# cominer_serial.net
KiCad netlist of a schematic drawn in EAGLE
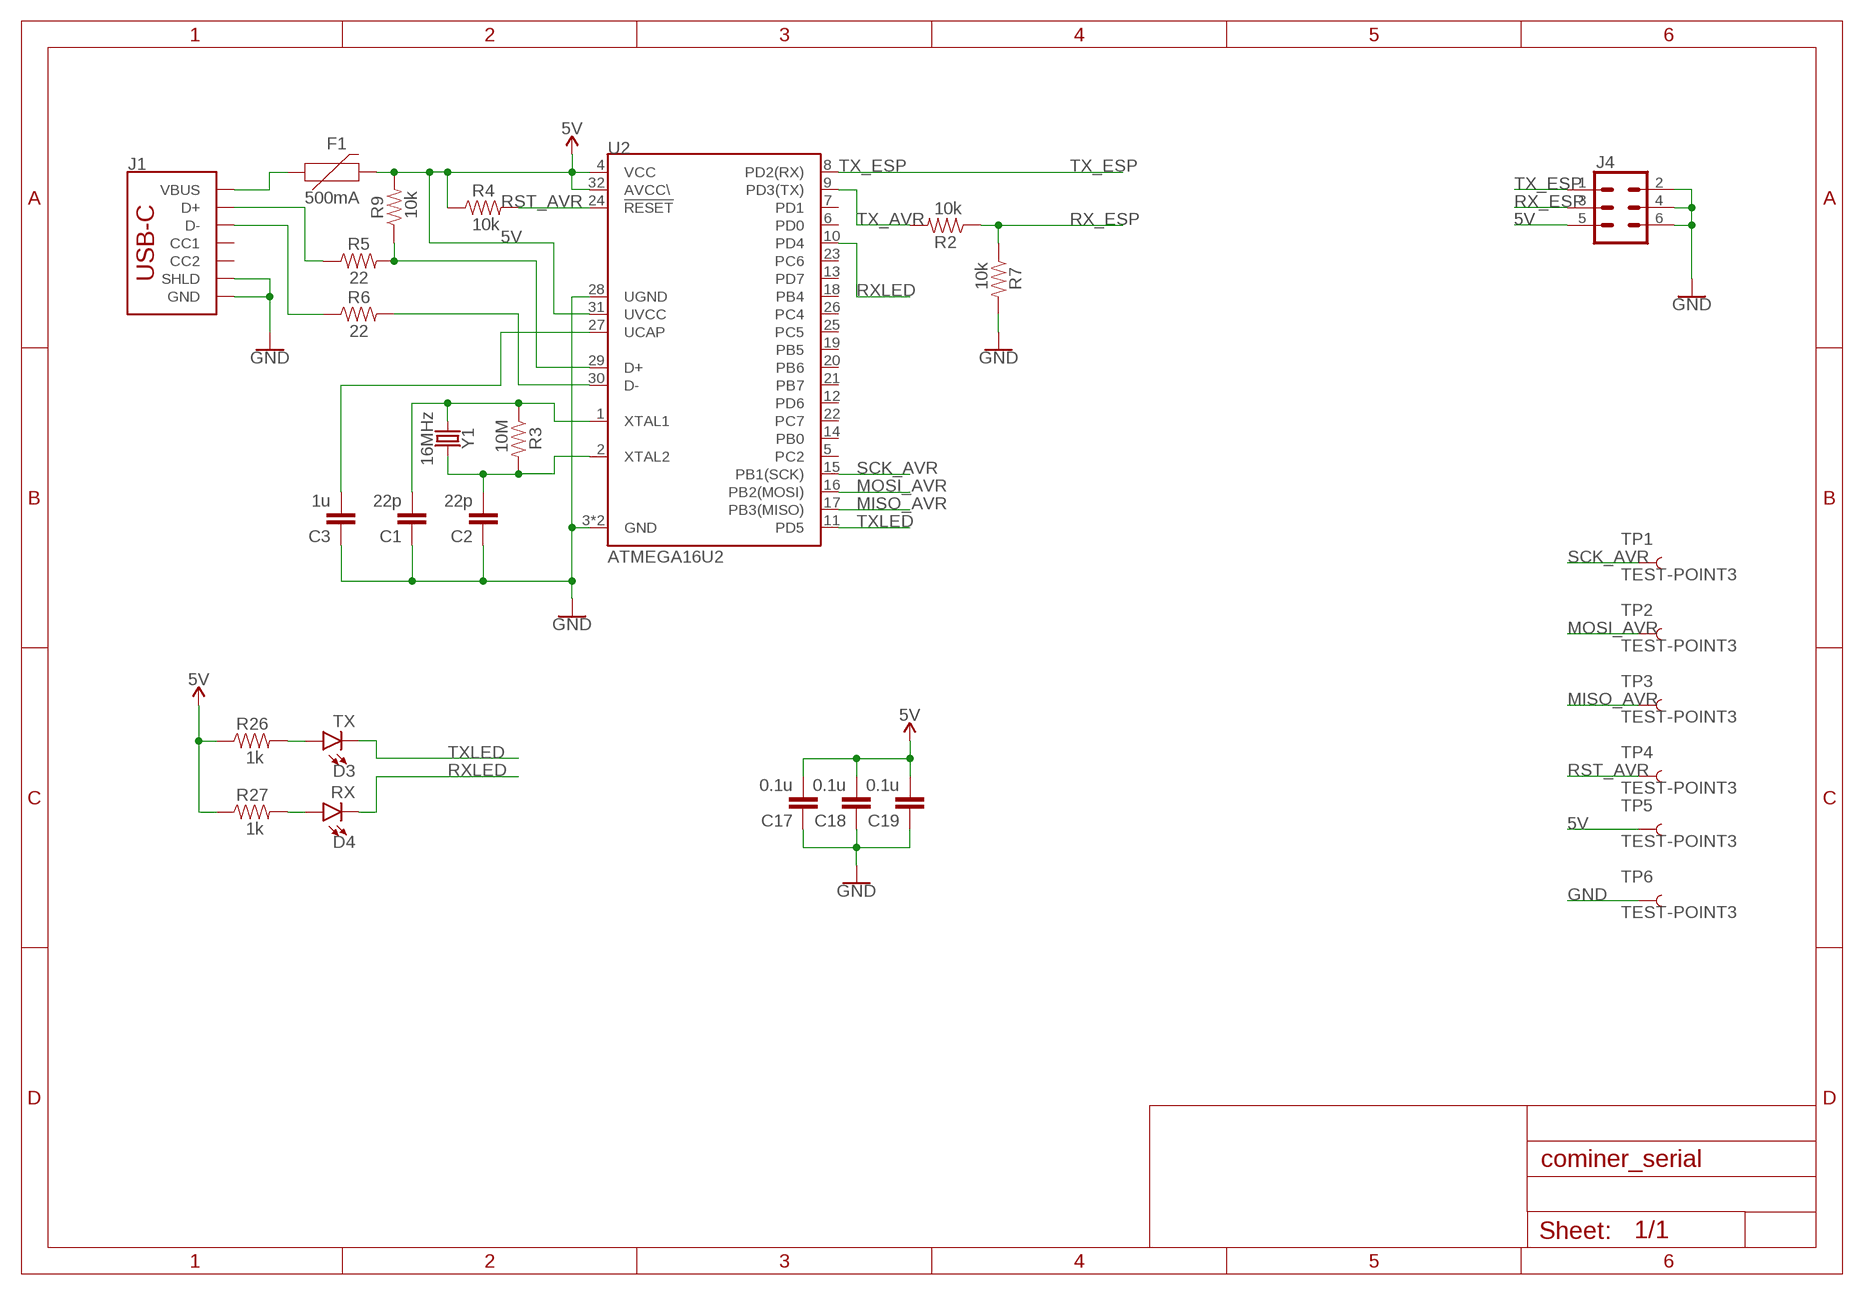
[diagram p0: schematic, sheet 1]

(export (version "E")
  (design (tool "Eeschema 10.0.6"))
  (components
    (comp (ref "C1")
      (value "22p")
      (footprint "eagle-import:0805")
      (libsource (lib "eagle-import") (part "CAP-0805"))
    )
    (comp (ref "C2")
      (value "22p")
      (footprint "eagle-import:0805")
      (libsource (lib "eagle-import") (part "CAP-0805"))
    )
    (comp (ref "C3")
      (value "1u")
      (footprint "eagle-import:0805")
      (libsource (lib "eagle-import") (part "CAP-0805"))
    )
    (comp (ref "C17")
      (value "0.1u")
      (footprint "eagle-import:0805")
      (libsource (lib "eagle-import") (part "CAP-0805"))
    )
    (comp (ref "C18")
      (value "0.1u")
      (footprint "eagle-import:0805")
      (libsource (lib "eagle-import") (part "CAP-0805"))
    )
    (comp (ref "C19")
      (value "0.1u")
      (footprint "eagle-import:0805")
      (libsource (lib "eagle-import") (part "CAP-0805"))
    )
    (comp (ref "D3")
      (value "TX")
      (footprint "eagle-import:LED-0603")
      (libsource (lib "eagle-import") (part "LED-YELLOW0603"))
    )
    (comp (ref "D4")
      (value "RX")
      (footprint "eagle-import:LED-0603")
      (libsource (lib "eagle-import") (part "LED-YELLOW0603"))
    )
    (comp (ref "F1")
      (value "500mA")
      (footprint "eagle-import:1812")
      (libsource (lib "eagle-import") (part "PPTC_16V_2.5A"))
    )
    (comp (ref "J1")
      (value "USB_C")
      (footprint "eagle-import:USB-C-16P-SMD")
      (libsource (lib "eagle-import") (part "USB_C"))
    )
    (comp (ref "J4")
      (value "CONN_03X2SHROUD")
      (footprint "eagle-import:2X3-SHROUDED")
      (libsource (lib "eagle-import") (part "CONN_03X2SHROUD"))
    )
    (comp (ref "R2")
      (value "10k")
      (footprint "eagle-import:0805")
      (libsource (lib "eagle-import") (part "RESISTOR0805"))
    )
    (comp (ref "R3")
      (value "10M")
      (footprint "eagle-import:0805")
      (libsource (lib "eagle-import") (part "RESISTOR0805"))
    )
    (comp (ref "R4")
      (value "10k")
      (footprint "eagle-import:0805")
      (libsource (lib "eagle-import") (part "RESISTOR0805"))
    )
    (comp (ref "R5")
      (value "22")
      (footprint "eagle-import:0805")
      (libsource (lib "eagle-import") (part "RESISTOR0805"))
    )
    (comp (ref "R6")
      (value "22")
      (footprint "eagle-import:0805")
      (libsource (lib "eagle-import") (part "RESISTOR0805"))
    )
    (comp (ref "R7")
      (value "10k")
      (footprint "eagle-import:0805")
      (libsource (lib "eagle-import") (part "RESISTOR0805"))
    )
    (comp (ref "R9")
      (value "10k")
      (footprint "eagle-import:0805")
      (libsource (lib "eagle-import") (part "RESISTOR0805"))
    )
    (comp (ref "R26")
      (value "1k")
      (footprint "eagle-import:0805")
      (libsource (lib "eagle-import") (part "RESISTOR0805"))
    )
    (comp (ref "R27")
      (value "1k")
      (footprint "eagle-import:0805")
      (libsource (lib "eagle-import") (part "RESISTOR0805"))
    )
    (comp (ref "TP1")
      (value "TEST-POINT3")
      (footprint "eagle-import:PAD.03X.03")
      (libsource (lib "eagle-import") (part "TEST-POINT3"))
    )
    (comp (ref "TP2")
      (value "TEST-POINT3")
      (footprint "eagle-import:PAD.03X.03")
      (libsource (lib "eagle-import") (part "TEST-POINT3"))
    )
    (comp (ref "TP3")
      (value "TEST-POINT3")
      (footprint "eagle-import:PAD.03X.03")
      (libsource (lib "eagle-import") (part "TEST-POINT3"))
    )
    (comp (ref "TP4")
      (value "TEST-POINT3")
      (footprint "eagle-import:PAD.03X.03")
      (libsource (lib "eagle-import") (part "TEST-POINT3"))
    )
    (comp (ref "TP5")
      (value "TEST-POINT3")
      (footprint "eagle-import:PAD.03X.03")
      (libsource (lib "eagle-import") (part "TEST-POINT3"))
    )
    (comp (ref "TP6")
      (value "TEST-POINT3")
      (footprint "eagle-import:PAD.03X.03")
      (libsource (lib "eagle-import") (part "TEST-POINT3"))
    )
    (comp (ref "U2")
      (value "ATMEGA16U2")
      (footprint "eagle-import:QFN32")
      (libsource (lib "eagle-import") (part "ATMEGA16U2"))
    )
    (comp (ref "Y1")
      (value "16MHz")
      (footprint "eagle-import:CRYSTAL-SMD-5X3.2-4PAD")
      (libsource (lib "eagle-import") (part "CRYSTAL-16MHZSMD-5X3.2"))
    )
  )
  (nets
    (net (code "1") (name "/MISO_AVR") (class "Default")
      (node (ref "TP3") (pin "P$1") (pinfunction "1_P$1") (pintype "bidirectional"))
      (node (ref "U2") (pin "17") (pinfunction "PB3(MISO)_17") (pintype "bidirectional"))
    )
    (net (code "2") (name "/MOSI_AVR") (class "Default")
      (node (ref "TP2") (pin "P$1") (pinfunction "1_P$1") (pintype "bidirectional"))
      (node (ref "U2") (pin "16") (pinfunction "PB2(MOSI)_16") (pintype "bidirectional"))
    )
    (net (code "3") (name "/RST_AVR") (class "Default")
      (node (ref "R4") (pin "2") (pinfunction "2_2") (pintype "passive"))
      (node (ref "TP4") (pin "P$1") (pinfunction "1_P$1") (pintype "bidirectional"))
      (node (ref "U2") (pin "24") (pinfunction "~{RESET}_24") (pintype "bidirectional"))
    )
    (net (code "4") (name "/RXLED") (class "Default")
      (node (ref "D4") (pin "C") (pinfunction "C_C") (pintype "passive"))
      (node (ref "U2") (pin "10") (pinfunction "PD4_10") (pintype "bidirectional"))
    )
    (net (code "5") (name "/RX_ESP") (class "Default")
      (node (ref "J4") (pin "3") (pinfunction "3_3") (pintype "bidirectional"))
      (node (ref "R2") (pin "1") (pinfunction "1_1") (pintype "passive"))
      (node (ref "R7") (pin "1") (pinfunction "1_1") (pintype "passive"))
    )
    (net (code "6") (name "/SCK_AVR") (class "Default")
      (node (ref "TP1") (pin "P$1") (pinfunction "1_P$1") (pintype "bidirectional"))
      (node (ref "U2") (pin "15") (pinfunction "PB1(SCK)_15") (pintype "bidirectional"))
    )
    (net (code "7") (name "/TXLED") (class "Default")
      (node (ref "D3") (pin "C") (pinfunction "C_C") (pintype "passive"))
      (node (ref "U2") (pin "11") (pinfunction "PD5_11") (pintype "bidirectional"))
    )
    (net (code "8") (name "/TX_AVR") (class "Default")
      (node (ref "R2") (pin "2") (pinfunction "2_2") (pintype "passive"))
      (node (ref "U2") (pin "9") (pinfunction "PD3(TX)_9") (pintype "bidirectional"))
    )
    (net (code "9") (name "/TX_ESP") (class "Default")
      (node (ref "J4") (pin "1") (pinfunction "1_1") (pintype "bidirectional"))
      (node (ref "U2") (pin "8") (pinfunction "PD2(RX)_8") (pintype "bidirectional"))
    )
    (net (code "10") (name "5V") (class "Default")
      (node (ref "C17") (pin "2") (pinfunction "2_2") (pintype "passive"))
      (node (ref "C18") (pin "2") (pinfunction "2_2") (pintype "passive"))
      (node (ref "C19") (pin "2") (pinfunction "2_2") (pintype "passive"))
      (node (ref "F1") (pin "2") (pinfunction "2_2") (pintype "bidirectional"))
      (node (ref "J4") (pin "5") (pinfunction "5_5") (pintype "bidirectional"))
      (node (ref "R26") (pin "1") (pinfunction "1_1") (pintype "passive"))
      (node (ref "R27") (pin "1") (pinfunction "1_1") (pintype "passive"))
      (node (ref "R4") (pin "1") (pinfunction "1_1") (pintype "passive"))
      (node (ref "R9") (pin "2") (pinfunction "2_2") (pintype "passive"))
      (node (ref "TP5") (pin "P$1") (pinfunction "1_P$1") (pintype "bidirectional"))
      (node (ref "U2") (pin "31") (pinfunction "UVCC_31") (pintype "bidirectional"))
      (node (ref "U2") (pin "32") (pinfunction "AVCC\\_32") (pintype "bidirectional"))
      (node (ref "U2") (pin "4") (pinfunction "VCC_4") (pintype "bidirectional"))
    )
    (net (code "11") (name "GND") (class "Default")
      (node (ref "C1") (pin "1") (pinfunction "1_1") (pintype "passive"))
      (node (ref "C17") (pin "1") (pinfunction "1_1") (pintype "passive"))
      (node (ref "C18") (pin "1") (pinfunction "1_1") (pintype "passive"))
      (node (ref "C19") (pin "1") (pinfunction "1_1") (pintype "passive"))
      (node (ref "C2") (pin "1") (pinfunction "1_1") (pintype "passive"))
      (node (ref "C3") (pin "1") (pinfunction "1_1") (pintype "passive"))
      (node (ref "J1") (pin "GND") (pinfunction "GND_GND") (pintype "bidirectional"))
      (node (ref "J1") (pin "GND2") (pinfunction "GND_GND2") (pintype "bidirectional"))
      (node (ref "J1") (pin "SHLD1") (pinfunction "SHLD_SHLD1") (pintype "bidirectional"))
      (node (ref "J1") (pin "SHLD2") (pinfunction "SHLD_SHLD2") (pintype "bidirectional"))
      (node (ref "J1") (pin "SHLD3") (pinfunction "SHLD_SHLD3") (pintype "bidirectional"))
      (node (ref "J1") (pin "SHLD4") (pinfunction "SHLD_SHLD4") (pintype "bidirectional"))
      (node (ref "J4") (pin "2") (pinfunction "2_2") (pintype "bidirectional"))
      (node (ref "J4") (pin "4") (pinfunction "4_4") (pintype "bidirectional"))
      (node (ref "J4") (pin "6") (pinfunction "6_6") (pintype "bidirectional"))
      (node (ref "R7") (pin "2") (pinfunction "2_2") (pintype "passive"))
      (node (ref "TP6") (pin "P$1") (pinfunction "1_P$1") (pintype "bidirectional"))
      (node (ref "U2") (pin "28") (pinfunction "UGND_28") (pintype "bidirectional"))
      (node (ref "U2") (pin "3") (pinfunction "GND_3") (pintype "bidirectional"))
      (node (ref "U2") (pin "EP") (pinfunction "GND_EP") (pintype "bidirectional"))
    )
    (net (code "12") (name "Net-(D3-PadA)") (class "Default")
      (node (ref "D3") (pin "A") (pinfunction "A_A") (pintype "passive"))
      (node (ref "R26") (pin "2") (pinfunction "2_2") (pintype "passive"))
    )
    (net (code "13") (name "Net-(D4-PadA)") (class "Default")
      (node (ref "D4") (pin "A") (pinfunction "A_A") (pintype "passive"))
      (node (ref "R27") (pin "2") (pinfunction "2_2") (pintype "passive"))
    )
    (net (code "14") (name "Net-(F1-Pad1)") (class "Default")
      (node (ref "F1") (pin "1") (pinfunction "1_1") (pintype "bidirectional"))
      (node (ref "J1") (pin "VBUS1") (pinfunction "VBUS_VBUS1") (pintype "bidirectional"))
      (node (ref "J1") (pin "VBUS2") (pinfunction "VBUS_VBUS2") (pintype "bidirectional"))
    )
    (net (code "15") (name "Net-(J1-D+-PadA6)") (class "Default")
      (node (ref "J1") (pin "A6") (pinfunction "D+_A6") (pintype "bidirectional"))
      (node (ref "J1") (pin "B6") (pinfunction "D+_B6") (pintype "bidirectional"))
      (node (ref "R5") (pin "1") (pinfunction "1_1") (pintype "passive"))
    )
    (net (code "16") (name "Net-(J1-D--PadA7)") (class "Default")
      (node (ref "J1") (pin "A7") (pinfunction "D-_A7") (pintype "bidirectional"))
      (node (ref "J1") (pin "B7") (pinfunction "D-_B7") (pintype "bidirectional"))
      (node (ref "R6") (pin "1") (pinfunction "1_1") (pintype "passive"))
    )
    (net (code "17") (name "Net-(U2-D+)") (class "Default")
      (node (ref "R5") (pin "2") (pinfunction "2_2") (pintype "passive"))
      (node (ref "R9") (pin "1") (pinfunction "1_1") (pintype "passive"))
      (node (ref "U2") (pin "29") (pinfunction "D+_29") (pintype "bidirectional"))
    )
    (net (code "18") (name "Net-(U2-D-)") (class "Default")
      (node (ref "R6") (pin "2") (pinfunction "2_2") (pintype "passive"))
      (node (ref "U2") (pin "30") (pinfunction "D-_30") (pintype "bidirectional"))
    )
    (net (code "19") (name "Net-(U2-UCAP)") (class "Default")
      (node (ref "C3") (pin "2") (pinfunction "2_2") (pintype "passive"))
      (node (ref "U2") (pin "27") (pinfunction "UCAP_27") (pintype "bidirectional"))
    )
    (net (code "20") (name "Net-(U2-XTAL1)") (class "Default")
      (node (ref "C1") (pin "2") (pinfunction "2_2") (pintype "passive"))
      (node (ref "R3") (pin "1") (pinfunction "1_1") (pintype "passive"))
      (node (ref "U2") (pin "1") (pinfunction "XTAL1_1") (pintype "bidirectional"))
      (node (ref "Y1") (pin "1") (pinfunction "1_1") (pintype "passive"))
    )
    (net (code "21") (name "Net-(U2-XTAL2)") (class "Default")
      (node (ref "C2") (pin "2") (pinfunction "2_2") (pintype "passive"))
      (node (ref "R3") (pin "2") (pinfunction "2_2") (pintype "passive"))
      (node (ref "U2") (pin "2") (pinfunction "XTAL2_2") (pintype "bidirectional"))
      (node (ref "Y1") (pin "3") (pinfunction "2_3") (pintype "passive"))
    )
    (net (code "22") (name "unconnected-(J1-CC1-PadA5)") (class "Default")
      (node (ref "J1") (pin "A5") (pinfunction "CC1_A5") (pintype "bidirectional"))
    )
    (net (code "23") (name "unconnected-(J1-CC2-PadB5)") (class "Default")
      (node (ref "J1") (pin "B5") (pinfunction "CC2_B5") (pintype "bidirectional"))
    )
    (net (code "24") (name "unconnected-(U2-PB0-Pad14)") (class "Default")
      (node (ref "U2") (pin "14") (pinfunction "PB0_14") (pintype "bidirectional"))
    )
    (net (code "25") (name "unconnected-(U2-PB4-Pad18)") (class "Default")
      (node (ref "U2") (pin "18") (pinfunction "PB4_18") (pintype "bidirectional"))
    )
    (net (code "26") (name "unconnected-(U2-PB5-Pad19)") (class "Default")
      (node (ref "U2") (pin "19") (pinfunction "PB5_19") (pintype "bidirectional"))
    )
    (net (code "27") (name "unconnected-(U2-PB6-Pad20)") (class "Default")
      (node (ref "U2") (pin "20") (pinfunction "PB6_20") (pintype "bidirectional"))
    )
    (net (code "28") (name "unconnected-(U2-PB7-Pad21)") (class "Default")
      (node (ref "U2") (pin "21") (pinfunction "PB7_21") (pintype "bidirectional"))
    )
    (net (code "29") (name "unconnected-(U2-PC2-Pad5)") (class "Default")
      (node (ref "U2") (pin "5") (pinfunction "PC2_5") (pintype "bidirectional"))
    )
    (net (code "30") (name "unconnected-(U2-PC4-Pad26)") (class "Default")
      (node (ref "U2") (pin "26") (pinfunction "PC4_26") (pintype "bidirectional"))
    )
    (net (code "31") (name "unconnected-(U2-PC5-Pad25)") (class "Default")
      (node (ref "U2") (pin "25") (pinfunction "PC5_25") (pintype "bidirectional"))
    )
    (net (code "32") (name "unconnected-(U2-PC6-Pad23)") (class "Default")
      (node (ref "U2") (pin "23") (pinfunction "PC6_23") (pintype "bidirectional"))
    )
    (net (code "33") (name "unconnected-(U2-PC7-Pad22)") (class "Default")
      (node (ref "U2") (pin "22") (pinfunction "PC7_22") (pintype "bidirectional"))
    )
    (net (code "34") (name "unconnected-(U2-PD0-Pad6)") (class "Default")
      (node (ref "U2") (pin "6") (pinfunction "PD0_6") (pintype "bidirectional"))
    )
    (net (code "35") (name "unconnected-(U2-PD1-Pad7)") (class "Default")
      (node (ref "U2") (pin "7") (pinfunction "PD1_7") (pintype "bidirectional"))
    )
    (net (code "36") (name "unconnected-(U2-PD6-Pad12)") (class "Default")
      (node (ref "U2") (pin "12") (pinfunction "PD6_12") (pintype "bidirectional"))
    )
    (net (code "37") (name "unconnected-(U2-PD7-Pad13)") (class "Default")
      (node (ref "U2") (pin "13") (pinfunction "PD7_13") (pintype "bidirectional"))
    )
  )
)
